# u.net
KiCad netlist of a schematic drawn in EAGLE
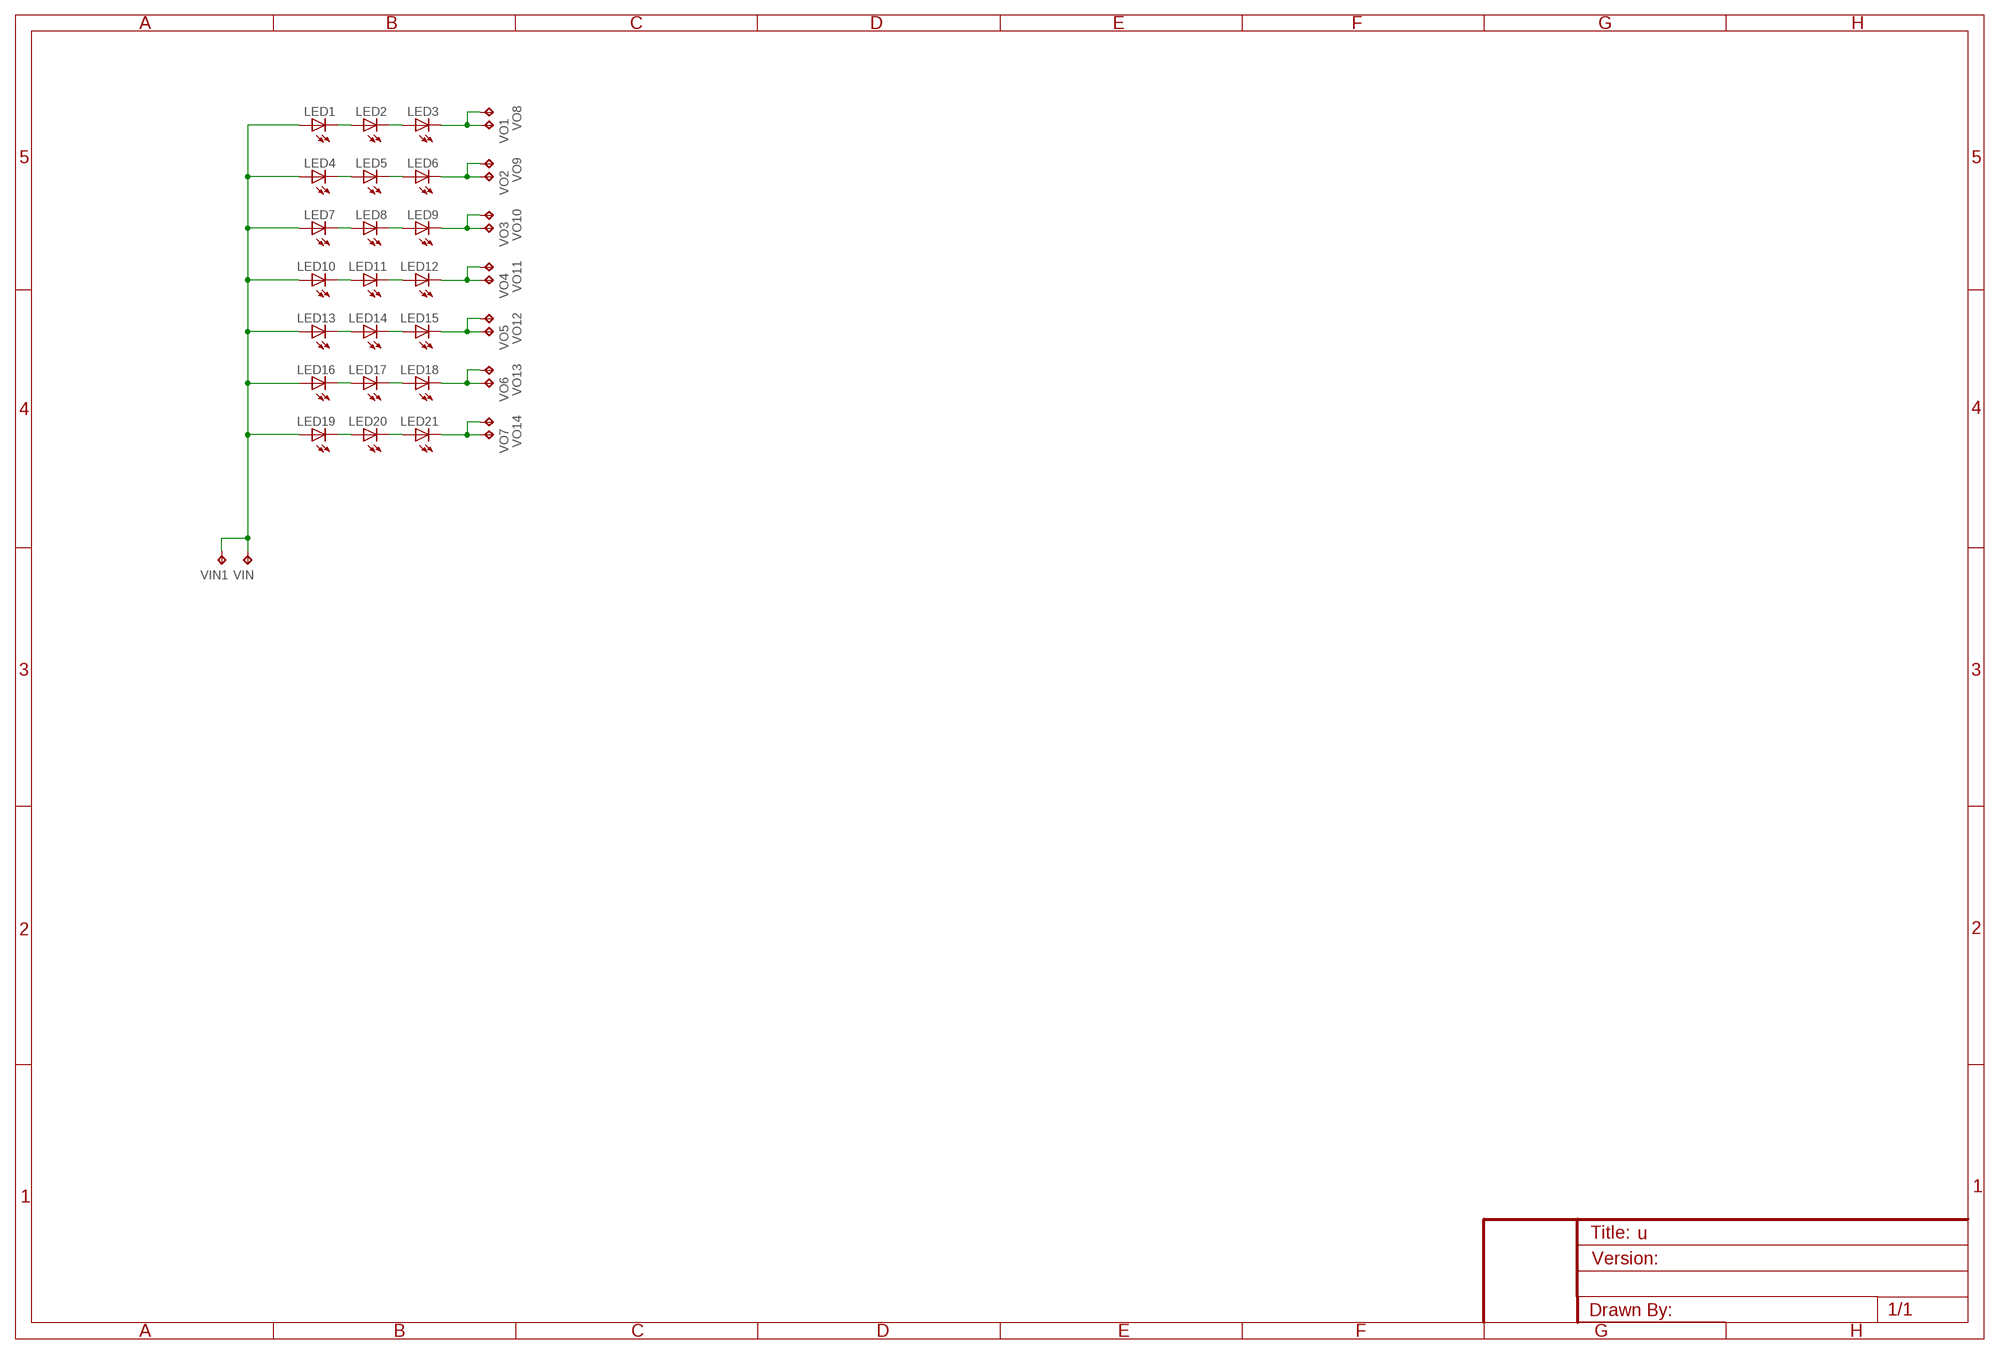
[diagram p0: schematic, sheet 1]

(export (version "E")
  (design (tool "Eeschema 10.0.6"))
  (components
    (comp (ref "LED1")
      (value "LED0805")
      (footprint "eagle-import:LED_0805")
      (libsource (lib "eagle-import") (part "LED0805"))
    )
    (comp (ref "LED2")
      (value "LED0805")
      (footprint "eagle-import:LED_0805")
      (libsource (lib "eagle-import") (part "LED0805"))
    )
    (comp (ref "LED3")
      (value "LED0805")
      (footprint "eagle-import:LED_0805")
      (libsource (lib "eagle-import") (part "LED0805"))
    )
    (comp (ref "LED4")
      (value "LED0805")
      (footprint "eagle-import:LED_0805")
      (libsource (lib "eagle-import") (part "LED0805"))
    )
    (comp (ref "LED5")
      (value "LED0805")
      (footprint "eagle-import:LED_0805")
      (libsource (lib "eagle-import") (part "LED0805"))
    )
    (comp (ref "LED6")
      (value "LED0805")
      (footprint "eagle-import:LED_0805")
      (libsource (lib "eagle-import") (part "LED0805"))
    )
    (comp (ref "LED7")
      (value "LED0805")
      (footprint "eagle-import:LED_0805")
      (libsource (lib "eagle-import") (part "LED0805"))
    )
    (comp (ref "LED8")
      (value "LED0805")
      (footprint "eagle-import:LED_0805")
      (libsource (lib "eagle-import") (part "LED0805"))
    )
    (comp (ref "LED9")
      (value "LED0805")
      (footprint "eagle-import:LED_0805")
      (libsource (lib "eagle-import") (part "LED0805"))
    )
    (comp (ref "LED10")
      (value "LED0805")
      (footprint "eagle-import:LED_0805")
      (libsource (lib "eagle-import") (part "LED0805"))
    )
    (comp (ref "LED11")
      (value "LED0805")
      (footprint "eagle-import:LED_0805")
      (libsource (lib "eagle-import") (part "LED0805"))
    )
    (comp (ref "LED12")
      (value "LED0805")
      (footprint "eagle-import:LED_0805")
      (libsource (lib "eagle-import") (part "LED0805"))
    )
    (comp (ref "LED13")
      (value "LED0805")
      (footprint "eagle-import:LED_0805")
      (libsource (lib "eagle-import") (part "LED0805"))
    )
    (comp (ref "LED14")
      (value "LED0805")
      (footprint "eagle-import:LED_0805")
      (libsource (lib "eagle-import") (part "LED0805"))
    )
    (comp (ref "LED15")
      (value "LED0805")
      (footprint "eagle-import:LED_0805")
      (libsource (lib "eagle-import") (part "LED0805"))
    )
    (comp (ref "LED16")
      (value "LED0805")
      (footprint "eagle-import:LED_0805")
      (libsource (lib "eagle-import") (part "LED0805"))
    )
    (comp (ref "LED17")
      (value "LED0805")
      (footprint "eagle-import:LED_0805")
      (libsource (lib "eagle-import") (part "LED0805"))
    )
    (comp (ref "LED18")
      (value "LED0805")
      (footprint "eagle-import:LED_0805")
      (libsource (lib "eagle-import") (part "LED0805"))
    )
    (comp (ref "LED19")
      (value "LED0805")
      (footprint "eagle-import:LED_0805")
      (libsource (lib "eagle-import") (part "LED0805"))
    )
    (comp (ref "LED20")
      (value "LED0805")
      (footprint "eagle-import:LED_0805")
      (libsource (lib "eagle-import") (part "LED0805"))
    )
    (comp (ref "LED21")
      (value "LED0805")
      (footprint "eagle-import:LED_0805")
      (libsource (lib "eagle-import") (part "LED0805"))
    )
    (comp (ref "VIN")
      (value "TEST_POINTPAD1-20")
      (footprint "eagle-import:P1-20")
      (libsource (lib "eagle-import") (part "TEST_POINTPAD1-20"))
    )
    (comp (ref "VIN1")
      (value "TEST_POINTPAD1-20")
      (footprint "eagle-import:P1-20")
      (libsource (lib "eagle-import") (part "TEST_POINTPAD1-20"))
    )
    (comp (ref "VO1")
      (value "TEST_POINTPAD1-20")
      (footprint "eagle-import:P1-20")
      (libsource (lib "eagle-import") (part "TEST_POINTPAD1-20"))
    )
    (comp (ref "VO2")
      (value "TEST_POINTPAD1-20")
      (footprint "eagle-import:P1-20")
      (libsource (lib "eagle-import") (part "TEST_POINTPAD1-20"))
    )
    (comp (ref "VO3")
      (value "TEST_POINTPAD1-20")
      (footprint "eagle-import:P1-20")
      (libsource (lib "eagle-import") (part "TEST_POINTPAD1-20"))
    )
    (comp (ref "VO4")
      (value "TEST_POINTPAD1-20")
      (footprint "eagle-import:P1-20")
      (libsource (lib "eagle-import") (part "TEST_POINTPAD1-20"))
    )
    (comp (ref "VO5")
      (value "TEST_POINTPAD1-20")
      (footprint "eagle-import:P1-20")
      (libsource (lib "eagle-import") (part "TEST_POINTPAD1-20"))
    )
    (comp (ref "VO6")
      (value "TEST_POINTPAD1-20")
      (footprint "eagle-import:P1-20")
      (libsource (lib "eagle-import") (part "TEST_POINTPAD1-20"))
    )
    (comp (ref "VO7")
      (value "TEST_POINTPAD1-20")
      (footprint "eagle-import:P1-20")
      (libsource (lib "eagle-import") (part "TEST_POINTPAD1-20"))
    )
    (comp (ref "VO8")
      (value "TEST_POINTPAD1-20")
      (footprint "eagle-import:P1-20")
      (libsource (lib "eagle-import") (part "TEST_POINTPAD1-20"))
    )
    (comp (ref "VO9")
      (value "TEST_POINTPAD1-20")
      (footprint "eagle-import:P1-20")
      (libsource (lib "eagle-import") (part "TEST_POINTPAD1-20"))
    )
    (comp (ref "VO10")
      (value "TEST_POINTPAD1-20")
      (footprint "eagle-import:P1-20")
      (libsource (lib "eagle-import") (part "TEST_POINTPAD1-20"))
    )
    (comp (ref "VO11")
      (value "TEST_POINTPAD1-20")
      (footprint "eagle-import:P1-20")
      (libsource (lib "eagle-import") (part "TEST_POINTPAD1-20"))
    )
    (comp (ref "VO12")
      (value "TEST_POINTPAD1-20")
      (footprint "eagle-import:P1-20")
      (libsource (lib "eagle-import") (part "TEST_POINTPAD1-20"))
    )
    (comp (ref "VO13")
      (value "TEST_POINTPAD1-20")
      (footprint "eagle-import:P1-20")
      (libsource (lib "eagle-import") (part "TEST_POINTPAD1-20"))
    )
    (comp (ref "VO14")
      (value "TEST_POINTPAD1-20")
      (footprint "eagle-import:P1-20")
      (libsource (lib "eagle-import") (part "TEST_POINTPAD1-20"))
    )
  )
  (nets
    (net (code "1") (name "Net-(LED1-PadA)") (class "Default")
      (node (ref "LED1") (pin "A") (pinfunction "A_A") (pintype "passive"))
      (node (ref "LED10") (pin "A") (pinfunction "A_A") (pintype "passive"))
      (node (ref "LED13") (pin "A") (pinfunction "A_A") (pintype "passive"))
      (node (ref "LED16") (pin "A") (pinfunction "A_A") (pintype "passive"))
      (node (ref "LED19") (pin "A") (pinfunction "A_A") (pintype "passive"))
      (node (ref "LED4") (pin "A") (pinfunction "A_A") (pintype "passive"))
      (node (ref "LED7") (pin "A") (pinfunction "A_A") (pintype "passive"))
      (node (ref "VIN") (pin "TP") (pinfunction "TP_TP") (pintype "input"))
      (node (ref "VIN1") (pin "TP") (pinfunction "TP_TP") (pintype "input"))
    )
    (net (code "2") (name "Net-(LED1-PadC)") (class "Default")
      (node (ref "LED1") (pin "C") (pinfunction "C_C") (pintype "passive"))
      (node (ref "LED2") (pin "A") (pinfunction "A_A") (pintype "passive"))
    )
    (net (code "3") (name "Net-(LED2-PadC)") (class "Default")
      (node (ref "LED2") (pin "C") (pinfunction "C_C") (pintype "passive"))
      (node (ref "LED3") (pin "A") (pinfunction "A_A") (pintype "passive"))
    )
    (net (code "4") (name "Net-(LED3-PadC)") (class "Default")
      (node (ref "LED3") (pin "C") (pinfunction "C_C") (pintype "passive"))
      (node (ref "VO1") (pin "TP") (pinfunction "TP_TP") (pintype "input"))
      (node (ref "VO8") (pin "TP") (pinfunction "TP_TP") (pintype "input"))
    )
    (net (code "5") (name "Net-(LED4-PadC)") (class "Default")
      (node (ref "LED4") (pin "C") (pinfunction "C_C") (pintype "passive"))
      (node (ref "LED5") (pin "A") (pinfunction "A_A") (pintype "passive"))
    )
    (net (code "6") (name "Net-(LED5-PadC)") (class "Default")
      (node (ref "LED5") (pin "C") (pinfunction "C_C") (pintype "passive"))
      (node (ref "LED6") (pin "A") (pinfunction "A_A") (pintype "passive"))
    )
    (net (code "7") (name "Net-(LED6-PadC)") (class "Default")
      (node (ref "LED6") (pin "C") (pinfunction "C_C") (pintype "passive"))
      (node (ref "VO2") (pin "TP") (pinfunction "TP_TP") (pintype "input"))
      (node (ref "VO9") (pin "TP") (pinfunction "TP_TP") (pintype "input"))
    )
    (net (code "8") (name "Net-(LED7-PadC)") (class "Default")
      (node (ref "LED7") (pin "C") (pinfunction "C_C") (pintype "passive"))
      (node (ref "LED8") (pin "A") (pinfunction "A_A") (pintype "passive"))
    )
    (net (code "9") (name "Net-(LED8-PadC)") (class "Default")
      (node (ref "LED8") (pin "C") (pinfunction "C_C") (pintype "passive"))
      (node (ref "LED9") (pin "A") (pinfunction "A_A") (pintype "passive"))
    )
    (net (code "10") (name "Net-(LED9-PadC)") (class "Default")
      (node (ref "LED9") (pin "C") (pinfunction "C_C") (pintype "passive"))
      (node (ref "VO10") (pin "TP") (pinfunction "TP_TP") (pintype "input"))
      (node (ref "VO3") (pin "TP") (pinfunction "TP_TP") (pintype "input"))
    )
    (net (code "11") (name "Net-(LED10-PadC)") (class "Default")
      (node (ref "LED10") (pin "C") (pinfunction "C_C") (pintype "passive"))
      (node (ref "LED11") (pin "A") (pinfunction "A_A") (pintype "passive"))
    )
    (net (code "12") (name "Net-(LED11-PadC)") (class "Default")
      (node (ref "LED11") (pin "C") (pinfunction "C_C") (pintype "passive"))
      (node (ref "LED12") (pin "A") (pinfunction "A_A") (pintype "passive"))
    )
    (net (code "13") (name "Net-(LED12-PadC)") (class "Default")
      (node (ref "LED12") (pin "C") (pinfunction "C_C") (pintype "passive"))
      (node (ref "VO11") (pin "TP") (pinfunction "TP_TP") (pintype "input"))
      (node (ref "VO4") (pin "TP") (pinfunction "TP_TP") (pintype "input"))
    )
    (net (code "14") (name "Net-(LED13-PadC)") (class "Default")
      (node (ref "LED13") (pin "C") (pinfunction "C_C") (pintype "passive"))
      (node (ref "LED14") (pin "A") (pinfunction "A_A") (pintype "passive"))
    )
    (net (code "15") (name "Net-(LED14-PadC)") (class "Default")
      (node (ref "LED14") (pin "C") (pinfunction "C_C") (pintype "passive"))
      (node (ref "LED15") (pin "A") (pinfunction "A_A") (pintype "passive"))
    )
    (net (code "16") (name "Net-(LED15-PadC)") (class "Default")
      (node (ref "LED15") (pin "C") (pinfunction "C_C") (pintype "passive"))
      (node (ref "VO12") (pin "TP") (pinfunction "TP_TP") (pintype "input"))
      (node (ref "VO5") (pin "TP") (pinfunction "TP_TP") (pintype "input"))
    )
    (net (code "17") (name "Net-(LED16-PadC)") (class "Default")
      (node (ref "LED16") (pin "C") (pinfunction "C_C") (pintype "passive"))
      (node (ref "LED17") (pin "A") (pinfunction "A_A") (pintype "passive"))
    )
    (net (code "18") (name "Net-(LED17-PadC)") (class "Default")
      (node (ref "LED17") (pin "C") (pinfunction "C_C") (pintype "passive"))
      (node (ref "LED18") (pin "A") (pinfunction "A_A") (pintype "passive"))
    )
    (net (code "19") (name "Net-(LED18-PadC)") (class "Default")
      (node (ref "LED18") (pin "C") (pinfunction "C_C") (pintype "passive"))
      (node (ref "VO13") (pin "TP") (pinfunction "TP_TP") (pintype "input"))
      (node (ref "VO6") (pin "TP") (pinfunction "TP_TP") (pintype "input"))
    )
    (net (code "20") (name "Net-(LED19-PadC)") (class "Default")
      (node (ref "LED19") (pin "C") (pinfunction "C_C") (pintype "passive"))
      (node (ref "LED20") (pin "A") (pinfunction "A_A") (pintype "passive"))
    )
    (net (code "21") (name "Net-(LED20-PadC)") (class "Default")
      (node (ref "LED20") (pin "C") (pinfunction "C_C") (pintype "passive"))
      (node (ref "LED21") (pin "A") (pinfunction "A_A") (pintype "passive"))
    )
    (net (code "22") (name "Net-(LED21-PadC)") (class "Default")
      (node (ref "LED21") (pin "C") (pinfunction "C_C") (pintype "passive"))
      (node (ref "VO14") (pin "TP") (pinfunction "TP_TP") (pintype "input"))
      (node (ref "VO7") (pin "TP") (pinfunction "TP_TP") (pintype "input"))
    )
  )
)
